# untitled.net
KiCad netlist of a schematic drawn in EAGLE
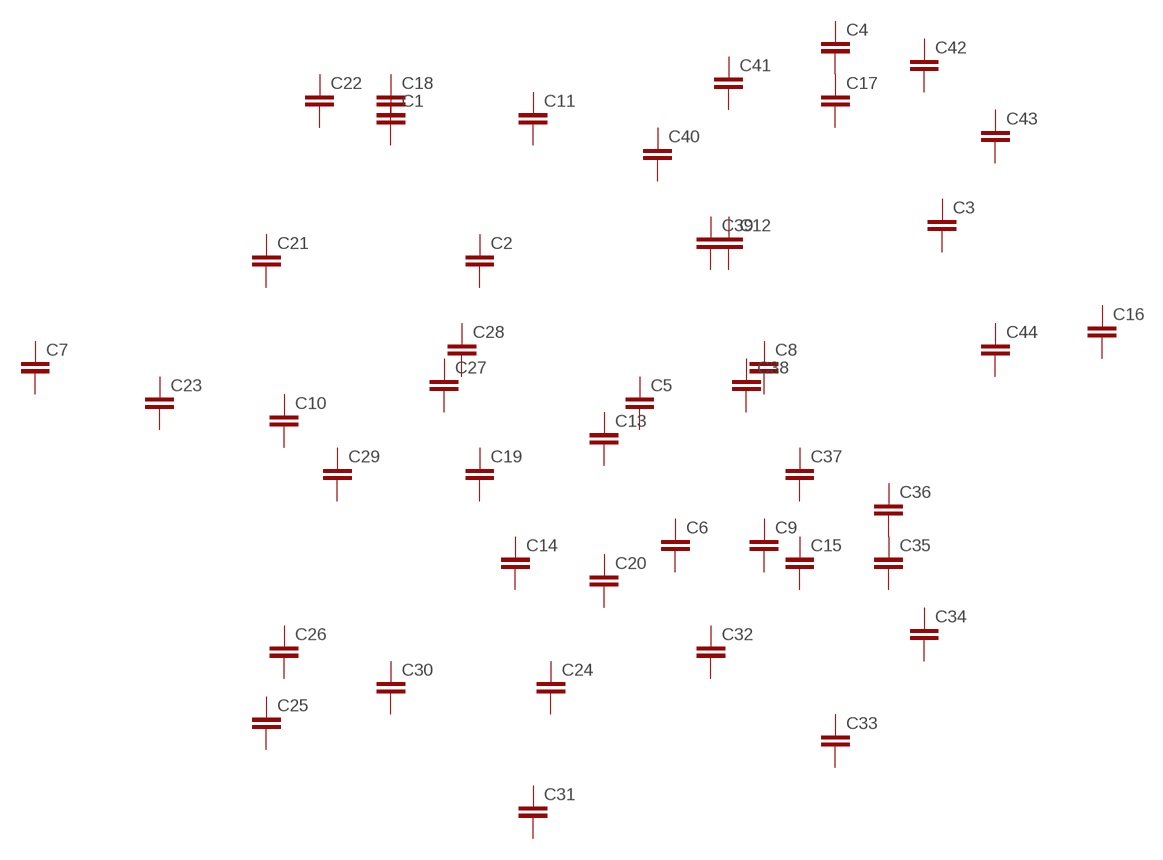
[diagram p0: schematic, sheet 1]

(export (version "E")
  (design (tool "Eeschema 10.0.6"))
  (components
    (comp (ref "C1")
      (value "C-EU025-024X044")
      (footprint "eagle-import:C025-024X044")
      (libsource (lib "eagle-import") (part "C-EU025-024X044"))
    )
    (comp (ref "C2")
      (value "C-EU025-024X044")
      (footprint "eagle-import:C025-024X044")
      (libsource (lib "eagle-import") (part "C-EU025-024X044"))
    )
    (comp (ref "C3")
      (value "C-EU025-024X044")
      (footprint "eagle-import:C025-024X044")
      (libsource (lib "eagle-import") (part "C-EU025-024X044"))
    )
    (comp (ref "C4")
      (value "C-EU025-024X044")
      (footprint "eagle-import:C025-024X044")
      (libsource (lib "eagle-import") (part "C-EU025-024X044"))
    )
    (comp (ref "C5")
      (value "C-EU025-024X044")
      (footprint "eagle-import:C025-024X044")
      (libsource (lib "eagle-import") (part "C-EU025-024X044"))
    )
    (comp (ref "C6")
      (value "C-EU025-024X044")
      (footprint "eagle-import:C025-024X044")
      (libsource (lib "eagle-import") (part "C-EU025-024X044"))
    )
    (comp (ref "C7")
      (value "C-EU025-024X044")
      (footprint "eagle-import:C025-024X044")
      (libsource (lib "eagle-import") (part "C-EU025-024X044"))
    )
    (comp (ref "C8")
      (value "C-EU025-024X044")
      (footprint "eagle-import:C025-024X044")
      (libsource (lib "eagle-import") (part "C-EU025-024X044"))
    )
    (comp (ref "C9")
      (value "C-EU025-024X044")
      (footprint "eagle-import:C025-024X044")
      (libsource (lib "eagle-import") (part "C-EU025-024X044"))
    )
    (comp (ref "C10")
      (value "C-EU025-024X044")
      (footprint "eagle-import:C025-024X044")
      (libsource (lib "eagle-import") (part "C-EU025-024X044"))
    )
    (comp (ref "C11")
      (value "C-EU025-024X044")
      (footprint "eagle-import:C025-024X044")
      (libsource (lib "eagle-import") (part "C-EU025-024X044"))
    )
    (comp (ref "C12")
      (value "C-EU025-024X044")
      (footprint "eagle-import:C025-024X044")
      (libsource (lib "eagle-import") (part "C-EU025-024X044"))
    )
    (comp (ref "C13")
      (value "C-EU025-024X044")
      (footprint "eagle-import:C025-024X044")
      (libsource (lib "eagle-import") (part "C-EU025-024X044"))
    )
    (comp (ref "C14")
      (value "C-EU025-024X044")
      (footprint "eagle-import:C025-024X044")
      (libsource (lib "eagle-import") (part "C-EU025-024X044"))
    )
    (comp (ref "C15")
      (value "C-EU025-024X044")
      (footprint "eagle-import:C025-024X044")
      (libsource (lib "eagle-import") (part "C-EU025-024X044"))
    )
    (comp (ref "C16")
      (value "C-EU025-024X044")
      (footprint "eagle-import:C025-024X044")
      (libsource (lib "eagle-import") (part "C-EU025-024X044"))
    )
    (comp (ref "C17")
      (value "C-EU025-024X044")
      (footprint "eagle-import:C025-024X044")
      (libsource (lib "eagle-import") (part "C-EU025-024X044"))
    )
    (comp (ref "C18")
      (value "C-EU025-024X044")
      (footprint "eagle-import:C025-024X044")
      (libsource (lib "eagle-import") (part "C-EU025-024X044"))
    )
    (comp (ref "C19")
      (value "C-EU025-024X044")
      (footprint "eagle-import:C025-024X044")
      (libsource (lib "eagle-import") (part "C-EU025-024X044"))
    )
    (comp (ref "C20")
      (value "C-EU025-024X044")
      (footprint "eagle-import:C025-024X044")
      (libsource (lib "eagle-import") (part "C-EU025-024X044"))
    )
    (comp (ref "C21")
      (value "C-EU025-024X044")
      (footprint "eagle-import:C025-024X044")
      (libsource (lib "eagle-import") (part "C-EU025-024X044"))
    )
    (comp (ref "C22")
      (value "C-EU025-024X044")
      (footprint "eagle-import:C025-024X044")
      (libsource (lib "eagle-import") (part "C-EU025-024X044"))
    )
    (comp (ref "C23")
      (value "C-EU025-024X044")
      (footprint "eagle-import:C025-024X044")
      (libsource (lib "eagle-import") (part "C-EU025-024X044"))
    )
    (comp (ref "C24")
      (value "C-EU025-024X044")
      (footprint "eagle-import:C025-024X044")
      (libsource (lib "eagle-import") (part "C-EU025-024X044"))
    )
    (comp (ref "C25")
      (value "C-EU025-024X044")
      (footprint "eagle-import:C025-024X044")
      (libsource (lib "eagle-import") (part "C-EU025-024X044"))
    )
    (comp (ref "C26")
      (value "C-EU025-024X044")
      (footprint "eagle-import:C025-024X044")
      (libsource (lib "eagle-import") (part "C-EU025-024X044"))
    )
    (comp (ref "C27")
      (value "C-EU025-024X044")
      (footprint "eagle-import:C025-024X044")
      (libsource (lib "eagle-import") (part "C-EU025-024X044"))
    )
    (comp (ref "C28")
      (value "C-EU025-024X044")
      (footprint "eagle-import:C025-024X044")
      (libsource (lib "eagle-import") (part "C-EU025-024X044"))
    )
    (comp (ref "C29")
      (value "C-EU025-024X044")
      (footprint "eagle-import:C025-024X044")
      (libsource (lib "eagle-import") (part "C-EU025-024X044"))
    )
    (comp (ref "C30")
      (value "C-EU025-024X044")
      (footprint "eagle-import:C025-024X044")
      (libsource (lib "eagle-import") (part "C-EU025-024X044"))
    )
    (comp (ref "C31")
      (value "C-EU025-024X044")
      (footprint "eagle-import:C025-024X044")
      (libsource (lib "eagle-import") (part "C-EU025-024X044"))
    )
    (comp (ref "C32")
      (value "C-EU025-024X044")
      (footprint "eagle-import:C025-024X044")
      (libsource (lib "eagle-import") (part "C-EU025-024X044"))
    )
    (comp (ref "C33")
      (value "C-EU025-024X044")
      (footprint "eagle-import:C025-024X044")
      (libsource (lib "eagle-import") (part "C-EU025-024X044"))
    )
    (comp (ref "C34")
      (value "C-EU025-024X044")
      (footprint "eagle-import:C025-024X044")
      (libsource (lib "eagle-import") (part "C-EU025-024X044"))
    )
    (comp (ref "C35")
      (value "C-EU025-024X044")
      (footprint "eagle-import:C025-024X044")
      (libsource (lib "eagle-import") (part "C-EU025-024X044"))
    )
    (comp (ref "C36")
      (value "C-EU025-024X044")
      (footprint "eagle-import:C025-024X044")
      (libsource (lib "eagle-import") (part "C-EU025-024X044"))
    )
    (comp (ref "C37")
      (value "C-EU025-024X044")
      (footprint "eagle-import:C025-024X044")
      (libsource (lib "eagle-import") (part "C-EU025-024X044"))
    )
    (comp (ref "C38")
      (value "C-EU025-024X044")
      (footprint "eagle-import:C025-024X044")
      (libsource (lib "eagle-import") (part "C-EU025-024X044"))
    )
    (comp (ref "C39")
      (value "C-EU025-024X044")
      (footprint "eagle-import:C025-024X044")
      (libsource (lib "eagle-import") (part "C-EU025-024X044"))
    )
    (comp (ref "C40")
      (value "C-EU025-024X044")
      (footprint "eagle-import:C025-024X044")
      (libsource (lib "eagle-import") (part "C-EU025-024X044"))
    )
    (comp (ref "C41")
      (value "C-EU025-024X044")
      (footprint "eagle-import:C025-024X044")
      (libsource (lib "eagle-import") (part "C-EU025-024X044"))
    )
    (comp (ref "C42")
      (value "C-EU025-024X044")
      (footprint "eagle-import:C025-024X044")
      (libsource (lib "eagle-import") (part "C-EU025-024X044"))
    )
    (comp (ref "C43")
      (value "C-EU025-024X044")
      (footprint "eagle-import:C025-024X044")
      (libsource (lib "eagle-import") (part "C-EU025-024X044"))
    )
    (comp (ref "C44")
      (value "C-EU025-024X044")
      (footprint "eagle-import:C025-024X044")
      (libsource (lib "eagle-import") (part "C-EU025-024X044"))
    )
  )
  (nets
    (net (code "1") (name "Net-(C17-Pad1)") (class "Default")
      (node (ref "C17") (pin "1") (pinfunction "1_1") (pintype "passive"))
      (node (ref "C4") (pin "2") (pinfunction "2_2") (pintype "passive"))
    )
    (net (code "2") (name "Net-(C35-Pad1)") (class "Default")
      (node (ref "C35") (pin "1") (pinfunction "1_1") (pintype "passive"))
      (node (ref "C36") (pin "2") (pinfunction "2_2") (pintype "passive"))
    )
    (net (code "3") (name "unconnected-(C1-Pad1)") (class "Default")
      (node (ref "C1") (pin "1") (pinfunction "1_1") (pintype "passive"))
    )
    (net (code "4") (name "unconnected-(C1-Pad2)") (class "Default")
      (node (ref "C1") (pin "2") (pinfunction "2_2") (pintype "passive"))
    )
    (net (code "5") (name "unconnected-(C2-Pad1)") (class "Default")
      (node (ref "C2") (pin "1") (pinfunction "1_1") (pintype "passive"))
    )
    (net (code "6") (name "unconnected-(C2-Pad2)") (class "Default")
      (node (ref "C2") (pin "2") (pinfunction "2_2") (pintype "passive"))
    )
    (net (code "7") (name "unconnected-(C3-Pad1)") (class "Default")
      (node (ref "C3") (pin "1") (pinfunction "1_1") (pintype "passive"))
    )
    (net (code "8") (name "unconnected-(C3-Pad2)") (class "Default")
      (node (ref "C3") (pin "2") (pinfunction "2_2") (pintype "passive"))
    )
    (net (code "9") (name "unconnected-(C4-Pad1)") (class "Default")
      (node (ref "C4") (pin "1") (pinfunction "1_1") (pintype "passive"))
    )
    (net (code "10") (name "unconnected-(C5-Pad1)") (class "Default")
      (node (ref "C5") (pin "1") (pinfunction "1_1") (pintype "passive"))
    )
    (net (code "11") (name "unconnected-(C5-Pad2)") (class "Default")
      (node (ref "C5") (pin "2") (pinfunction "2_2") (pintype "passive"))
    )
    (net (code "12") (name "unconnected-(C6-Pad1)") (class "Default")
      (node (ref "C6") (pin "1") (pinfunction "1_1") (pintype "passive"))
    )
    (net (code "13") (name "unconnected-(C6-Pad2)") (class "Default")
      (node (ref "C6") (pin "2") (pinfunction "2_2") (pintype "passive"))
    )
    (net (code "14") (name "unconnected-(C7-Pad1)") (class "Default")
      (node (ref "C7") (pin "1") (pinfunction "1_1") (pintype "passive"))
    )
    (net (code "15") (name "unconnected-(C7-Pad2)") (class "Default")
      (node (ref "C7") (pin "2") (pinfunction "2_2") (pintype "passive"))
    )
    (net (code "16") (name "unconnected-(C8-Pad1)") (class "Default")
      (node (ref "C8") (pin "1") (pinfunction "1_1") (pintype "passive"))
    )
    (net (code "17") (name "unconnected-(C8-Pad2)") (class "Default")
      (node (ref "C8") (pin "2") (pinfunction "2_2") (pintype "passive"))
    )
    (net (code "18") (name "unconnected-(C9-Pad1)") (class "Default")
      (node (ref "C9") (pin "1") (pinfunction "1_1") (pintype "passive"))
    )
    (net (code "19") (name "unconnected-(C9-Pad2)") (class "Default")
      (node (ref "C9") (pin "2") (pinfunction "2_2") (pintype "passive"))
    )
    (net (code "20") (name "unconnected-(C10-Pad1)") (class "Default")
      (node (ref "C10") (pin "1") (pinfunction "1_1") (pintype "passive"))
    )
    (net (code "21") (name "unconnected-(C10-Pad2)") (class "Default")
      (node (ref "C10") (pin "2") (pinfunction "2_2") (pintype "passive"))
    )
    (net (code "22") (name "unconnected-(C11-Pad1)") (class "Default")
      (node (ref "C11") (pin "1") (pinfunction "1_1") (pintype "passive"))
    )
    (net (code "23") (name "unconnected-(C11-Pad2)") (class "Default")
      (node (ref "C11") (pin "2") (pinfunction "2_2") (pintype "passive"))
    )
    (net (code "24") (name "unconnected-(C12-Pad1)") (class "Default")
      (node (ref "C12") (pin "1") (pinfunction "1_1") (pintype "passive"))
    )
    (net (code "25") (name "unconnected-(C12-Pad2)") (class "Default")
      (node (ref "C12") (pin "2") (pinfunction "2_2") (pintype "passive"))
    )
    (net (code "26") (name "unconnected-(C13-Pad1)") (class "Default")
      (node (ref "C13") (pin "1") (pinfunction "1_1") (pintype "passive"))
    )
    (net (code "27") (name "unconnected-(C13-Pad2)") (class "Default")
      (node (ref "C13") (pin "2") (pinfunction "2_2") (pintype "passive"))
    )
    (net (code "28") (name "unconnected-(C14-Pad1)") (class "Default")
      (node (ref "C14") (pin "1") (pinfunction "1_1") (pintype "passive"))
    )
    (net (code "29") (name "unconnected-(C14-Pad2)") (class "Default")
      (node (ref "C14") (pin "2") (pinfunction "2_2") (pintype "passive"))
    )
    (net (code "30") (name "unconnected-(C15-Pad1)") (class "Default")
      (node (ref "C15") (pin "1") (pinfunction "1_1") (pintype "passive"))
    )
    (net (code "31") (name "unconnected-(C15-Pad2)") (class "Default")
      (node (ref "C15") (pin "2") (pinfunction "2_2") (pintype "passive"))
    )
    (net (code "32") (name "unconnected-(C16-Pad1)") (class "Default")
      (node (ref "C16") (pin "1") (pinfunction "1_1") (pintype "passive"))
    )
    (net (code "33") (name "unconnected-(C16-Pad2)") (class "Default")
      (node (ref "C16") (pin "2") (pinfunction "2_2") (pintype "passive"))
    )
    (net (code "34") (name "unconnected-(C17-Pad2)") (class "Default")
      (node (ref "C17") (pin "2") (pinfunction "2_2") (pintype "passive"))
    )
    (net (code "35") (name "unconnected-(C18-Pad1)") (class "Default")
      (node (ref "C18") (pin "1") (pinfunction "1_1") (pintype "passive"))
    )
    (net (code "36") (name "unconnected-(C18-Pad2)") (class "Default")
      (node (ref "C18") (pin "2") (pinfunction "2_2") (pintype "passive"))
    )
    (net (code "37") (name "unconnected-(C19-Pad1)") (class "Default")
      (node (ref "C19") (pin "1") (pinfunction "1_1") (pintype "passive"))
    )
    (net (code "38") (name "unconnected-(C19-Pad2)") (class "Default")
      (node (ref "C19") (pin "2") (pinfunction "2_2") (pintype "passive"))
    )
    (net (code "39") (name "unconnected-(C20-Pad1)") (class "Default")
      (node (ref "C20") (pin "1") (pinfunction "1_1") (pintype "passive"))
    )
    (net (code "40") (name "unconnected-(C20-Pad2)") (class "Default")
      (node (ref "C20") (pin "2") (pinfunction "2_2") (pintype "passive"))
    )
    (net (code "41") (name "unconnected-(C21-Pad1)") (class "Default")
      (node (ref "C21") (pin "1") (pinfunction "1_1") (pintype "passive"))
    )
    (net (code "42") (name "unconnected-(C21-Pad2)") (class "Default")
      (node (ref "C21") (pin "2") (pinfunction "2_2") (pintype "passive"))
    )
    (net (code "43") (name "unconnected-(C22-Pad1)") (class "Default")
      (node (ref "C22") (pin "1") (pinfunction "1_1") (pintype "passive"))
    )
    (net (code "44") (name "unconnected-(C22-Pad2)") (class "Default")
      (node (ref "C22") (pin "2") (pinfunction "2_2") (pintype "passive"))
    )
    (net (code "45") (name "unconnected-(C23-Pad1)") (class "Default")
      (node (ref "C23") (pin "1") (pinfunction "1_1") (pintype "passive"))
    )
    (net (code "46") (name "unconnected-(C23-Pad2)") (class "Default")
      (node (ref "C23") (pin "2") (pinfunction "2_2") (pintype "passive"))
    )
    (net (code "47") (name "unconnected-(C24-Pad1)") (class "Default")
      (node (ref "C24") (pin "1") (pinfunction "1_1") (pintype "passive"))
    )
    (net (code "48") (name "unconnected-(C24-Pad2)") (class "Default")
      (node (ref "C24") (pin "2") (pinfunction "2_2") (pintype "passive"))
    )
    (net (code "49") (name "unconnected-(C25-Pad1)") (class "Default")
      (node (ref "C25") (pin "1") (pinfunction "1_1") (pintype "passive"))
    )
    (net (code "50") (name "unconnected-(C25-Pad2)") (class "Default")
      (node (ref "C25") (pin "2") (pinfunction "2_2") (pintype "passive"))
    )
    (net (code "51") (name "unconnected-(C26-Pad1)") (class "Default")
      (node (ref "C26") (pin "1") (pinfunction "1_1") (pintype "passive"))
    )
    (net (code "52") (name "unconnected-(C26-Pad2)") (class "Default")
      (node (ref "C26") (pin "2") (pinfunction "2_2") (pintype "passive"))
    )
    (net (code "53") (name "unconnected-(C27-Pad1)") (class "Default")
      (node (ref "C27") (pin "1") (pinfunction "1_1") (pintype "passive"))
    )
    (net (code "54") (name "unconnected-(C27-Pad2)") (class "Default")
      (node (ref "C27") (pin "2") (pinfunction "2_2") (pintype "passive"))
    )
    (net (code "55") (name "unconnected-(C28-Pad1)") (class "Default")
      (node (ref "C28") (pin "1") (pinfunction "1_1") (pintype "passive"))
    )
    (net (code "56") (name "unconnected-(C28-Pad2)") (class "Default")
      (node (ref "C28") (pin "2") (pinfunction "2_2") (pintype "passive"))
    )
    (net (code "57") (name "unconnected-(C29-Pad1)") (class "Default")
      (node (ref "C29") (pin "1") (pinfunction "1_1") (pintype "passive"))
    )
    (net (code "58") (name "unconnected-(C29-Pad2)") (class "Default")
      (node (ref "C29") (pin "2") (pinfunction "2_2") (pintype "passive"))
    )
    (net (code "59") (name "unconnected-(C30-Pad1)") (class "Default")
      (node (ref "C30") (pin "1") (pinfunction "1_1") (pintype "passive"))
    )
    (net (code "60") (name "unconnected-(C30-Pad2)") (class "Default")
      (node (ref "C30") (pin "2") (pinfunction "2_2") (pintype "passive"))
    )
    (net (code "61") (name "unconnected-(C31-Pad1)") (class "Default")
      (node (ref "C31") (pin "1") (pinfunction "1_1") (pintype "passive"))
    )
    (net (code "62") (name "unconnected-(C31-Pad2)") (class "Default")
      (node (ref "C31") (pin "2") (pinfunction "2_2") (pintype "passive"))
    )
    (net (code "63") (name "unconnected-(C32-Pad1)") (class "Default")
      (node (ref "C32") (pin "1") (pinfunction "1_1") (pintype "passive"))
    )
    (net (code "64") (name "unconnected-(C32-Pad2)") (class "Default")
      (node (ref "C32") (pin "2") (pinfunction "2_2") (pintype "passive"))
    )
    (net (code "65") (name "unconnected-(C33-Pad1)") (class "Default")
      (node (ref "C33") (pin "1") (pinfunction "1_1") (pintype "passive"))
    )
    (net (code "66") (name "unconnected-(C33-Pad2)") (class "Default")
      (node (ref "C33") (pin "2") (pinfunction "2_2") (pintype "passive"))
    )
    (net (code "67") (name "unconnected-(C34-Pad1)") (class "Default")
      (node (ref "C34") (pin "1") (pinfunction "1_1") (pintype "passive"))
    )
    (net (code "68") (name "unconnected-(C34-Pad2)") (class "Default")
      (node (ref "C34") (pin "2") (pinfunction "2_2") (pintype "passive"))
    )
    (net (code "69") (name "unconnected-(C35-Pad2)") (class "Default")
      (node (ref "C35") (pin "2") (pinfunction "2_2") (pintype "passive"))
    )
    (net (code "70") (name "unconnected-(C36-Pad1)") (class "Default")
      (node (ref "C36") (pin "1") (pinfunction "1_1") (pintype "passive"))
    )
    (net (code "71") (name "unconnected-(C37-Pad1)") (class "Default")
      (node (ref "C37") (pin "1") (pinfunction "1_1") (pintype "passive"))
    )
    (net (code "72") (name "unconnected-(C37-Pad2)") (class "Default")
      (node (ref "C37") (pin "2") (pinfunction "2_2") (pintype "passive"))
    )
    (net (code "73") (name "unconnected-(C38-Pad1)") (class "Default")
      (node (ref "C38") (pin "1") (pinfunction "1_1") (pintype "passive"))
    )
    (net (code "74") (name "unconnected-(C38-Pad2)") (class "Default")
      (node (ref "C38") (pin "2") (pinfunction "2_2") (pintype "passive"))
    )
    (net (code "75") (name "unconnected-(C39-Pad1)") (class "Default")
      (node (ref "C39") (pin "1") (pinfunction "1_1") (pintype "passive"))
    )
    (net (code "76") (name "unconnected-(C39-Pad2)") (class "Default")
      (node (ref "C39") (pin "2") (pinfunction "2_2") (pintype "passive"))
    )
    (net (code "77") (name "unconnected-(C40-Pad1)") (class "Default")
      (node (ref "C40") (pin "1") (pinfunction "1_1") (pintype "passive"))
    )
    (net (code "78") (name "unconnected-(C40-Pad2)") (class "Default")
      (node (ref "C40") (pin "2") (pinfunction "2_2") (pintype "passive"))
    )
    (net (code "79") (name "unconnected-(C41-Pad1)") (class "Default")
      (node (ref "C41") (pin "1") (pinfunction "1_1") (pintype "passive"))
    )
    (net (code "80") (name "unconnected-(C41-Pad2)") (class "Default")
      (node (ref "C41") (pin "2") (pinfunction "2_2") (pintype "passive"))
    )
    (net (code "81") (name "unconnected-(C42-Pad1)") (class "Default")
      (node (ref "C42") (pin "1") (pinfunction "1_1") (pintype "passive"))
    )
    (net (code "82") (name "unconnected-(C42-Pad2)") (class "Default")
      (node (ref "C42") (pin "2") (pinfunction "2_2") (pintype "passive"))
    )
    (net (code "83") (name "unconnected-(C43-Pad1)") (class "Default")
      (node (ref "C43") (pin "1") (pinfunction "1_1") (pintype "passive"))
    )
    (net (code "84") (name "unconnected-(C43-Pad2)") (class "Default")
      (node (ref "C43") (pin "2") (pinfunction "2_2") (pintype "passive"))
    )
    (net (code "85") (name "unconnected-(C44-Pad1)") (class "Default")
      (node (ref "C44") (pin "1") (pinfunction "1_1") (pintype "passive"))
    )
    (net (code "86") (name "unconnected-(C44-Pad2)") (class "Default")
      (node (ref "C44") (pin "2") (pinfunction "2_2") (pintype "passive"))
    )
  )
)
